# Digit_Board.net
KiCad netlist of a schematic drawn in Altium Designer
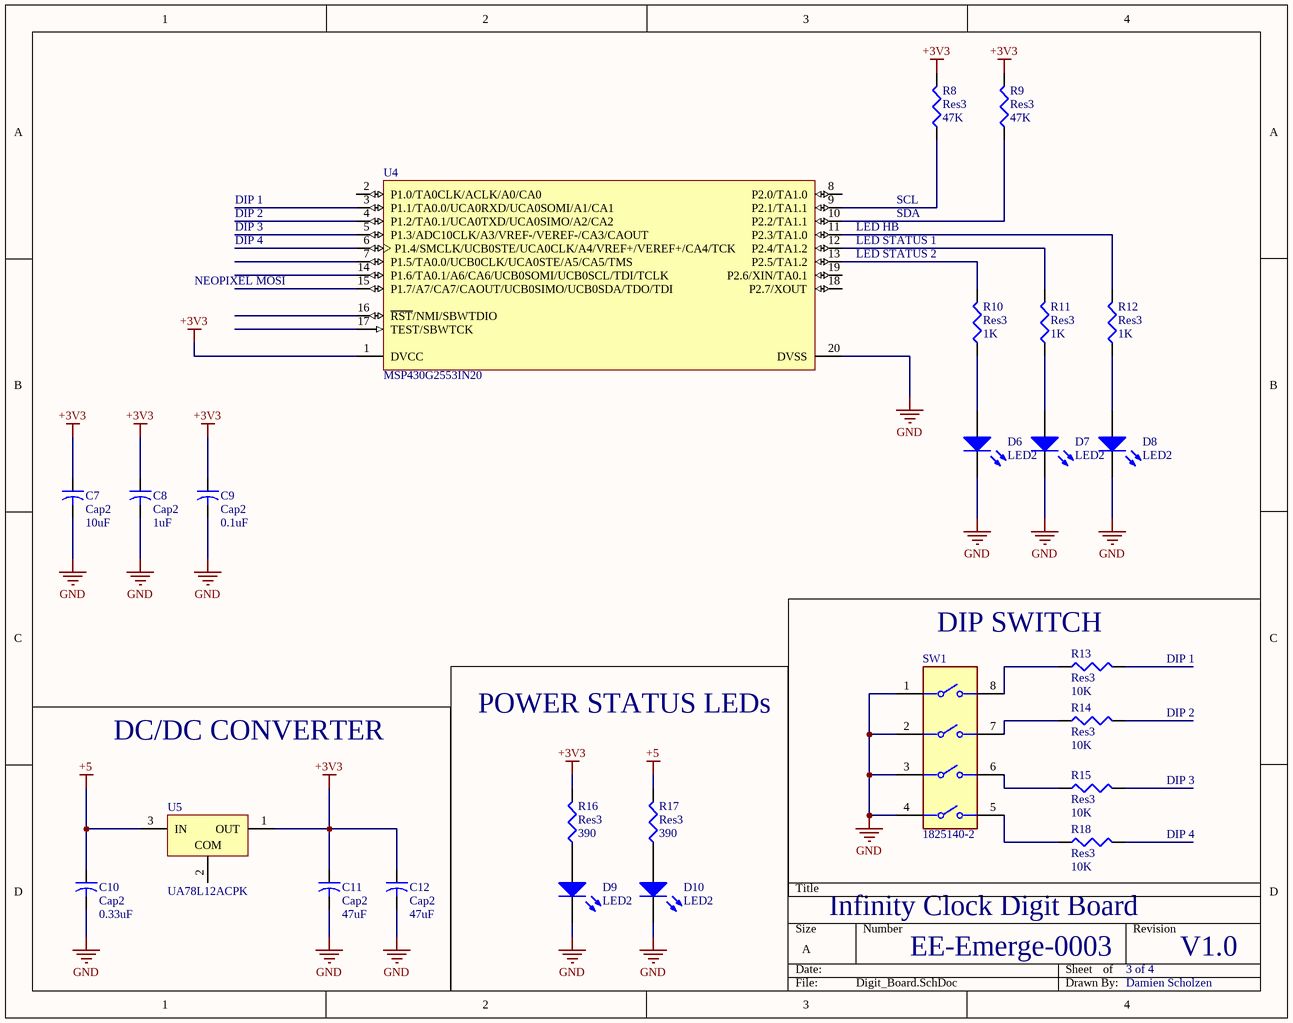
[diagram p0: Digit_Board.SchDoc]

(export (version "E")
  (design (tool "Eeschema 10.0.6"))
  (components
    (comp (ref "C7")
      (value "Cap2")
      (footprint "C0805")
      (description "Capacitor")
      (fields (field (name "ALTIUM_VALUE") "10uF") (field (name "PUBLISHER") "Altium Limited"))
      (libsource (lib "EE_Emerge_SkillsProject (1)") (part "Cap2"))
    )
    (comp (ref "C8")
      (value "Cap2")
      (footprint "C0805")
      (description "Capacitor")
      (fields (field (name "ALTIUM_VALUE") "1uF") (field (name "PUBLISHER") "Altium Limited"))
      (libsource (lib "EE_Emerge_SkillsProject (1)") (part "Cap2_1"))
    )
    (comp (ref "C9")
      (value "Cap2")
      (footprint "C0805")
      (description "Capacitor")
      (fields (field (name "ALTIUM_VALUE") "0.1uF") (field (name "PUBLISHER") "Altium Limited"))
      (libsource (lib "EE_Emerge_SkillsProject (1)") (part "Cap2_2"))
    )
    (comp (ref "C10")
      (value "Cap2")
      (footprint "C0805")
      (description "Capacitor")
      (fields (field (name "ALTIUM_VALUE") "0.33uF") (field (name "PUBLISHER") "Altium Limited"))
      (libsource (lib "EE_Emerge_SkillsProject (1)") (part "Cap2_4"))
    )
    (comp (ref "C11")
      (value "Cap2")
      (footprint "C0805")
      (description "Capacitor")
      (fields (field (name "ALTIUM_VALUE") "47uF") (field (name "PUBLISHER") "Altium Limited"))
      (libsource (lib "EE_Emerge_SkillsProject (1)") (part "Cap2_5"))
    )
    (comp (ref "C12")
      (value "Cap2")
      (footprint "C0805")
      (description "Capacitor")
      (fields (field (name "ALTIUM_VALUE") "47uF") (field (name "PUBLISHER") "Altium Limited"))
      (libsource (lib "EE_Emerge_SkillsProject (1)") (part "Cap2_5"))
    )
    (comp (ref "D6")
      (value "LED2")
      (footprint "3.2X1.6X1.1")
      (description "Typical RED, GREEN, YELLOW, AMBER GaAs LED")
      (fields (field (name "PUBLISHER") "Altium Limited"))
      (libsource (lib "EE_Emerge_SkillsProject (1)") (part "LED2"))
    )
    (comp (ref "D7")
      (value "LED2")
      (footprint "3.2X1.6X1.1")
      (description "Typical RED, GREEN, YELLOW, AMBER GaAs LED")
      (fields (field (name "PUBLISHER") "Altium Limited"))
      (libsource (lib "EE_Emerge_SkillsProject (1)") (part "LED2"))
    )
    (comp (ref "D8")
      (value "LED2")
      (footprint "3.2X1.6X1.1")
      (description "Typical RED, GREEN, YELLOW, AMBER GaAs LED")
      (fields (field (name "PUBLISHER") "Altium Limited"))
      (libsource (lib "EE_Emerge_SkillsProject (1)") (part "LED2"))
    )
    (comp (ref "D9")
      (value "LED2")
      (footprint "3.2X1.6X1.1")
      (description "Typical RED, GREEN, YELLOW, AMBER GaAs LED")
      (fields (field (name "PUBLISHER") "Altium Limited"))
      (libsource (lib "EE_Emerge_SkillsProject (1)") (part "LED2"))
    )
    (comp (ref "D10")
      (value "LED2")
      (footprint "3.2X1.6X1.1")
      (description "Typical RED, GREEN, YELLOW, AMBER GaAs LED")
      (fields (field (name "PUBLISHER") "Altium Limited"))
      (libsource (lib "EE_Emerge_SkillsProject (1)") (part "LED2"))
    )
    (comp (ref "R8")
      (value "Res3")
      (footprint "6-0805_N")
      (description "Resistor")
      (fields (field (name "ALTIUM_VALUE") "47K") (field (name "PUBLISHER") "Altium Limited"))
      (libsource (lib "EE_Emerge_SkillsProject (1)") (part "Res3_1"))
    )
    (comp (ref "R9")
      (value "Res3")
      (footprint "6-0805_N")
      (description "Resistor")
      (fields (field (name "ALTIUM_VALUE") "47K") (field (name "PUBLISHER") "Altium Limited"))
      (libsource (lib "EE_Emerge_SkillsProject (1)") (part "Res3_1"))
    )
    (comp (ref "R10")
      (value "Res3")
      (footprint "6-0805_N")
      (description "Resistor")
      (fields (field (name "ALTIUM_VALUE") "1K") (field (name "PUBLISHER") "Altium Limited"))
      (libsource (lib "EE_Emerge_SkillsProject (1)") (part "Res3_2"))
    )
    (comp (ref "R11")
      (value "Res3")
      (footprint "6-0805_N")
      (description "Resistor")
      (fields (field (name "ALTIUM_VALUE") "1K") (field (name "PUBLISHER") "Altium Limited"))
      (libsource (lib "EE_Emerge_SkillsProject (1)") (part "Res3_2"))
    )
    (comp (ref "R12")
      (value "Res3")
      (footprint "6-0805_N")
      (description "Resistor")
      (fields (field (name "ALTIUM_VALUE") "1K") (field (name "PUBLISHER") "Altium Limited"))
      (libsource (lib "EE_Emerge_SkillsProject (1)") (part "Res3_2"))
    )
    (comp (ref "R13")
      (value "Res3")
      (footprint "6-0805_N")
      (description "Resistor")
      (fields (field (name "ALTIUM_VALUE") "10K") (field (name "PUBLISHER") "Altium Limited"))
      (libsource (lib "EE_Emerge_SkillsProject (1)") (part "Res3_3"))
    )
    (comp (ref "R14")
      (value "Res3")
      (footprint "6-0805_N")
      (description "Resistor")
      (fields (field (name "ALTIUM_VALUE") "10K") (field (name "PUBLISHER") "Altium Limited"))
      (libsource (lib "EE_Emerge_SkillsProject (1)") (part "Res3_3"))
    )
    (comp (ref "R15")
      (value "Res3")
      (footprint "6-0805_N")
      (description "Resistor")
      (fields (field (name "ALTIUM_VALUE") "10K") (field (name "PUBLISHER") "Altium Limited"))
      (libsource (lib "EE_Emerge_SkillsProject (1)") (part "Res3_3"))
    )
    (comp (ref "R16")
      (value "Res3")
      (footprint "6-0805_N")
      (description "Resistor")
      (fields (field (name "ALTIUM_VALUE") "390") (field (name "PUBLISHER") "Altium Limited"))
      (libsource (lib "EE_Emerge_SkillsProject (1)") (part "Res3_4"))
    )
    (comp (ref "R17")
      (value "Res3")
      (footprint "6-0805_N")
      (description "Resistor")
      (fields (field (name "ALTIUM_VALUE") "390") (field (name "PUBLISHER") "Altium Limited"))
      (libsource (lib "EE_Emerge_SkillsProject (1)") (part "Res3_4"))
    )
    (comp (ref "R18")
      (value "Res3")
      (footprint "6-0805_N")
      (description "Resistor")
      (fields (field (name "ALTIUM_VALUE") "10K") (field (name "PUBLISHER") "Altium Limited"))
      (libsource (lib "EE_Emerge_SkillsProject (1)") (part "Res3_3"))
    )
    (comp (ref "SW1")
      (value "1825140-2")
      (footprint "FP-1825140-2-MFG")
      (description "SWITCH SLIDE DIP SPST 25MA 24V")
      (libsource (lib "Altium Content Vault") (part "ee767f539d9274548732198086319ae"))
    )
    (comp (ref "U4")
      (value "MSP430G2553IN20")
      (footprint "N0020A")
      (fields (field (name "MANUFACTURER") "Texas Instruments"))
      (libsource (lib "EE_Emerge_SkillsProject (1)") (part "CMP-0365-00184-2"))
    )
    (comp (ref "U5")
      (value "UA78L12ACPK")
      (footprint "PK0003A_M")
      (libsource (lib "EE_Emerge_SkillsProject (1)") (part "CMP-0324-00094-3"))
    )
  )
  (nets
    (net (code "1") (name "+3V3") (class "Default")
      (node (ref "C11") (pin "1") (pinfunction "1_1") (pintype "passive"))
      (node (ref "C12") (pin "1") (pinfunction "1_1") (pintype "passive"))
      (node (ref "C7") (pin "1") (pinfunction "1_1") (pintype "passive"))
      (node (ref "C8") (pin "1") (pinfunction "1_1") (pintype "passive"))
      (node (ref "C9") (pin "1") (pinfunction "1_1") (pintype "passive"))
      (node (ref "R16") (pin "2") (pinfunction "2_2") (pintype "passive"))
      (node (ref "R8") (pin "2") (pinfunction "2_2") (pintype "passive"))
      (node (ref "R9") (pin "2") (pinfunction "2_2") (pintype "passive"))
      (node (ref "U4") (pin "1") (pinfunction "DVCC_1") (pintype "power_in"))
      (node (ref "U5") (pin "1") (pinfunction "OUT_1") (pintype "power_in"))
    )
    (net (code "2") (name "+5") (class "Default")
      (node (ref "C10") (pin "1") (pinfunction "1_1") (pintype "passive"))
      (node (ref "R17") (pin "2") (pinfunction "2_2") (pintype "passive"))
      (node (ref "U5") (pin "3") (pinfunction "IN_3") (pintype "power_in"))
    )
    (net (code "3") (name "GND") (class "Default")
      (node (ref "C10") (pin "2") (pinfunction "2_2") (pintype "passive"))
      (node (ref "C11") (pin "2") (pinfunction "2_2") (pintype "passive"))
      (node (ref "C12") (pin "2") (pinfunction "2_2") (pintype "passive"))
      (node (ref "C7") (pin "2") (pinfunction "2_2") (pintype "passive"))
      (node (ref "C8") (pin "2") (pinfunction "2_2") (pintype "passive"))
      (node (ref "C9") (pin "2") (pinfunction "2_2") (pintype "passive"))
      (node (ref "D10") (pin "2") (pinfunction "K_2") (pintype "passive"))
      (node (ref "D6") (pin "2") (pinfunction "K_2") (pintype "passive"))
      (node (ref "D7") (pin "2") (pinfunction "K_2") (pintype "passive"))
      (node (ref "D8") (pin "2") (pinfunction "K_2") (pintype "passive"))
      (node (ref "D9") (pin "2") (pinfunction "K_2") (pintype "passive"))
      (node (ref "SW1") (pin "1") (pinfunction "1_1") (pintype "passive"))
      (node (ref "SW1") (pin "2") (pinfunction "2_2") (pintype "passive"))
      (node (ref "SW1") (pin "3") (pinfunction "3_3") (pintype "passive"))
      (node (ref "SW1") (pin "4") (pinfunction "4_4") (pintype "passive"))
      (node (ref "U4") (pin "20") (pinfunction "DVSS_20") (pintype "power_in"))
    )
    (net (code "4") (name "Net-(D6-A)") (class "Default")
      (node (ref "D6") (pin "1") (pinfunction "A_1") (pintype "passive"))
      (node (ref "R10") (pin "1") (pinfunction "1_1") (pintype "passive"))
    )
    (net (code "5") (name "Net-(D7-A)") (class "Default")
      (node (ref "D7") (pin "1") (pinfunction "A_1") (pintype "passive"))
      (node (ref "R11") (pin "1") (pinfunction "1_1") (pintype "passive"))
    )
    (net (code "6") (name "Net-(D8-A)") (class "Default")
      (node (ref "D8") (pin "1") (pinfunction "A_1") (pintype "passive"))
      (node (ref "R12") (pin "1") (pinfunction "1_1") (pintype "passive"))
    )
    (net (code "7") (name "Net-(D9-A)") (class "Default")
      (node (ref "D9") (pin "1") (pinfunction "A_1") (pintype "passive"))
      (node (ref "R16") (pin "1") (pinfunction "1_1") (pintype "passive"))
    )
    (net (code "8") (name "Net-(D10-A)") (class "Default")
      (node (ref "D10") (pin "1") (pinfunction "A_1") (pintype "passive"))
      (node (ref "R17") (pin "1") (pinfunction "1_1") (pintype "passive"))
    )
    (net (code "9") (name "Net-(R13-Pad1)") (class "Default")
      (node (ref "R13") (pin "1") (pinfunction "1_1") (pintype "passive"))
      (node (ref "SW1") (pin "8") (pinfunction "8_8") (pintype "passive"))
    )
    (net (code "10") (name "Net-(R14-Pad1)") (class "Default")
      (node (ref "R14") (pin "1") (pinfunction "1_1") (pintype "passive"))
      (node (ref "SW1") (pin "7") (pinfunction "7_7") (pintype "passive"))
    )
    (net (code "11") (name "Net-(R15-Pad1)") (class "Default")
      (node (ref "R15") (pin "1") (pinfunction "1_1") (pintype "passive"))
      (node (ref "SW1") (pin "6") (pinfunction "6_6") (pintype "passive"))
    )
    (net (code "12") (name "Net-(R18-Pad1)") (class "Default")
      (node (ref "R18") (pin "1") (pinfunction "1_1") (pintype "passive"))
      (node (ref "SW1") (pin "5") (pinfunction "5_5") (pintype "passive"))
    )
    (net (code "13") (name "Net-(U4-P2.1{slash}TA1.1)") (class "Default")
      (node (ref "R8") (pin "1") (pinfunction "1_1") (pintype "passive"))
      (node (ref "U4") (pin "9") (pinfunction "P2.1/TA1.1_9") (pintype "bidirectional"))
    )
    (net (code "14") (name "Net-(U4-P2.2{slash}TA1.1)") (class "Default")
      (node (ref "R9") (pin "1") (pinfunction "1_1") (pintype "passive"))
      (node (ref "U4") (pin "10") (pinfunction "P2.2/TA1.1_10") (pintype "bidirectional"))
    )
    (net (code "15") (name "Net-(U4-P2.3{slash}TA1.0)") (class "Default")
      (node (ref "R12") (pin "2") (pinfunction "2_2") (pintype "passive"))
      (node (ref "U4") (pin "11") (pinfunction "P2.3/TA1.0_11") (pintype "bidirectional"))
    )
    (net (code "16") (name "Net-(U4-P2.4{slash}TA1.2)") (class "Default")
      (node (ref "R11") (pin "2") (pinfunction "2_2") (pintype "passive"))
      (node (ref "U4") (pin "12") (pinfunction "P2.4/TA1.2_12") (pintype "bidirectional"))
    )
    (net (code "17") (name "Net-(U4-P2.5{slash}TA1.2)") (class "Default")
      (node (ref "R10") (pin "2") (pinfunction "2_2") (pintype "passive"))
      (node (ref "U4") (pin "13") (pinfunction "P2.5/TA1.2_13") (pintype "bidirectional"))
    )
    (net (code "18") (name "unconnected-(R13-Pad2)") (class "Default")
      (node (ref "R13") (pin "2") (pinfunction "2_2") (pintype "passive"))
    )
    (net (code "19") (name "unconnected-(R14-Pad2)") (class "Default")
      (node (ref "R14") (pin "2") (pinfunction "2_2") (pintype "passive"))
    )
    (net (code "20") (name "unconnected-(R15-Pad2)") (class "Default")
      (node (ref "R15") (pin "2") (pinfunction "2_2") (pintype "passive"))
    )
    (net (code "21") (name "unconnected-(R18-Pad2)") (class "Default")
      (node (ref "R18") (pin "2") (pinfunction "2_2") (pintype "passive"))
    )
    (net (code "22") (name "unconnected-(U4-P1.0{slash}TA0CLK{slash}ACLK{slash}A0{slash}CA0-Pad2)") (class "Default")
      (node (ref "U4") (pin "2") (pinfunction "P1.0/TA0CLK/ACLK/A0/CA0_2") (pintype "bidirectional"))
    )
    (net (code "23") (name "unconnected-(U4-P1.1{slash}TA0.0{slash}UCA0RXD{slash}UCA0SOMI{slash}A1{slash}CA1-Pad3)") (class "Default")
      (node (ref "U4") (pin "3") (pinfunction "P1.1/TA0.0/UCA0RXD/UCA0SOMI/A1/CA1_3") (pintype "bidirectional"))
    )
    (net (code "24") (name "unconnected-(U4-P1.2{slash}TA0.1{slash}UCA0TXD{slash}UCA0SIMO{slash}A2{slash}CA2-Pad4)") (class "Default")
      (node (ref "U4") (pin "4") (pinfunction "P1.2/TA0.1/UCA0TXD/UCA0SIMO/A2/CA2_4") (pintype "bidirectional"))
    )
    (net (code "25") (name "unconnected-(U4-P1.3{slash}ADC10CLK{slash}A3{slash}VREF-{slash}VEREF-{slash}CA3{slash}CAOUT-Pad5)") (class "Default")
      (node (ref "U4") (pin "5") (pinfunction "P1.3/ADC10CLK/A3/VREF-/VEREF-/CA3/CAOUT_5") (pintype "bidirectional"))
    )
    (net (code "26") (name "unconnected-(U4-P1.4{slash}SMCLK{slash}UCB0STE{slash}UCA0CLK{slash}A4{slash}VREF+{slash}VEREF+{slash}CA4{slash}TCK-Pad6)") (class "Default")
      (node (ref "U4") (pin "6") (pinfunction "P1.4/SMCLK/UCB0STE/UCA0CLK/A4/VREF+/VEREF+/CA4/TCK_6") (pintype "bidirectional"))
    )
    (net (code "27") (name "unconnected-(U4-P1.5{slash}TA0.0{slash}UCB0CLK{slash}UCA0STE{slash}A5{slash}CA5{slash}TMS-Pad7)") (class "Default")
      (node (ref "U4") (pin "7") (pinfunction "P1.5/TA0.0/UCB0CLK/UCA0STE/A5/CA5/TMS_7") (pintype "bidirectional"))
    )
    (net (code "28") (name "unconnected-(U4-P1.6{slash}TA0.1{slash}A6{slash}CA6{slash}UCB0SOMI{slash}UCB0SCL{slash}TDI{slash}TCLK-Pad14)") (class "Default")
      (node (ref "U4") (pin "14") (pinfunction "P1.6/TA0.1/A6/CA6/UCB0SOMI/UCB0SCL/TDI/TCLK_14") (pintype "bidirectional"))
    )
    (net (code "29") (name "unconnected-(U4-P1.7{slash}A7{slash}CA7{slash}CAOUT{slash}UCB0SIMO{slash}UCB0SDA{slash}TDO{slash}TDI-Pad15)") (class "Default")
      (node (ref "U4") (pin "15") (pinfunction "P1.7/A7/CA7/CAOUT/UCB0SIMO/UCB0SDA/TDO/TDI_15") (pintype "bidirectional"))
    )
    (net (code "30") (name "unconnected-(U4-P2.0{slash}TA1.0-Pad8)") (class "Default")
      (node (ref "U4") (pin "8") (pinfunction "P2.0/TA1.0_8") (pintype "bidirectional"))
    )
    (net (code "31") (name "unconnected-(U4-P2.6{slash}XIN{slash}TA0.1-Pad19)") (class "Default")
      (node (ref "U4") (pin "19") (pinfunction "P2.6/XIN/TA0.1_19") (pintype "bidirectional"))
    )
    (net (code "32") (name "unconnected-(U4-P2.7{slash}XOUT-Pad18)") (class "Default")
      (node (ref "U4") (pin "18") (pinfunction "P2.7/XOUT_18") (pintype "bidirectional"))
    )
    (net (code "33") (name "unconnected-(U4-TEST{slash}SBWTCK-Pad17)") (class "Default")
      (node (ref "U4") (pin "17") (pinfunction "TEST/SBWTCK_17") (pintype "input"))
    )
    (net (code "34") (name "unconnected-(U4-~{RST}{slash}NMI{slash}SBWTDIO-Pad16)") (class "Default")
      (node (ref "U4") (pin "16") (pinfunction "~{RST}/NMI/SBWTDIO_16") (pintype "bidirectional"))
    )
    (net (code "35") (name "unconnected-(U5-COM-Pad2)") (class "Default")
      (node (ref "U5") (pin "2") (pinfunction "COM_2") (pintype "power_in"))
    )
  )
)
